# Filtrado_y_amplificaci_n.net
KiCad netlist of a schematic drawn in Altium Designer
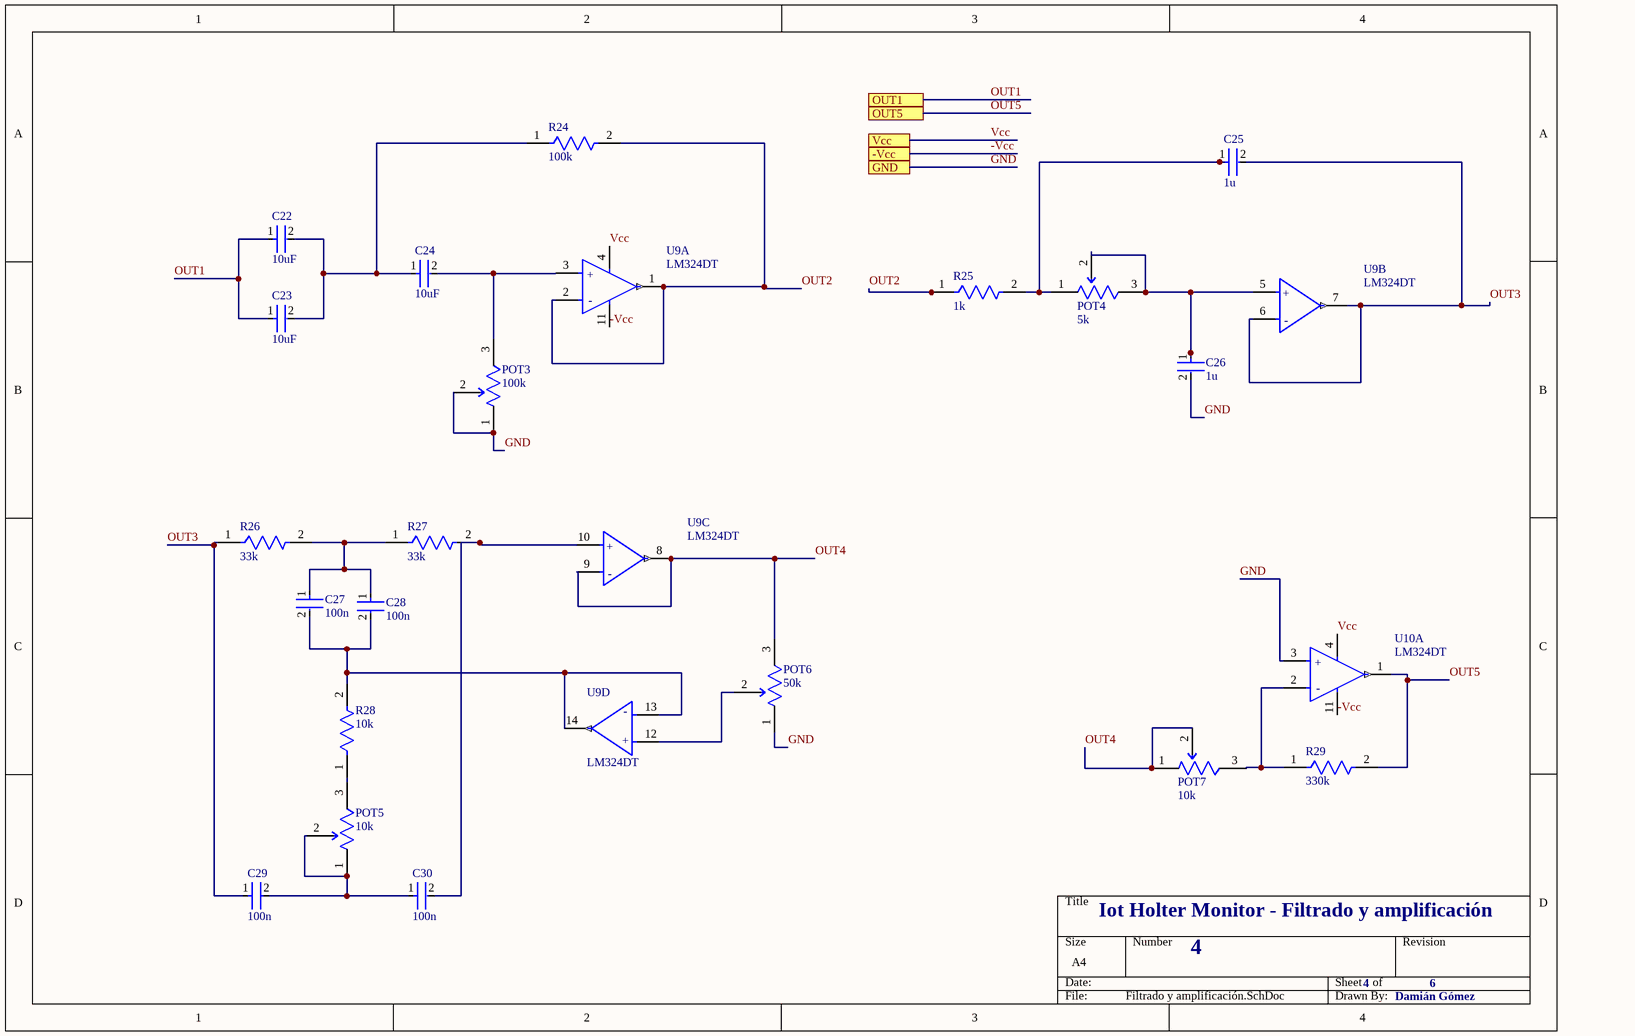
[diagram p0: Filtrado y amplificación.SchDoc]

(export (version "E")
  (design (tool "Eeschema 10.0.6"))
  (components
    (comp (ref "C22")
      (value "10uF")
      (footprint "FP-CL31-IPC_C")
      (description "Cap Ceramic 10uF 500V C0G ±5% SMD 1206 +125°C Embossed T/R")
      (fields (field (name "TOLERANCE") "5%"))
      (libsource (lib "Altium Content Vault") (part "b4654b650e69147ec39a6b967a45e02"))
    )
    (comp (ref "C23")
      (value "10uF")
      (footprint "FP-CL31-IPC_C")
      (description "Cap Ceramic 10uF 500V C0G ±5% SMD 1206 +125°C Embossed T/R")
      (fields (field (name "TOLERANCE") "5%"))
      (libsource (lib "Altium Content Vault") (part "b4654b650e69147ec39a6b967a45e02"))
    )
    (comp (ref "C24")
      (value "10uF")
      (footprint "FP-CL31-IPC_C")
      (description "Cap Ceramic 10uF 500V C0G ±5% SMD 1206 +125°C Embossed T/R")
      (fields (field (name "TOLERANCE") "5%"))
      (libsource (lib "Altium Content Vault") (part "b4654b650e69147ec39a6b967a45e02"))
    )
    (comp (ref "C25")
      (value "1u")
      (footprint "FP-CL31-IPC_C")
      (description "Cap Ceramic 1uF 500V C0G ±5% SMD 1206 +125°C Embossed T/R")
      (fields (field (name "TOLERANCE") "5%"))
      (libsource (lib "Altium Content Vault") (part "b4654b650e69147ec39a6b967a45e02"))
    )
    (comp (ref "C26")
      (value "1u")
      (footprint "FP-CL31-IPC_C")
      (description "Cap Ceramic 1uF 500V C0G ±5% SMD 1206 +125°C Embossed T/R")
      (fields (field (name "TOLERANCE") "5%"))
      (libsource (lib "Altium Content Vault") (part "b4654b650e69147ec39a6b967a45e02"))
    )
    (comp (ref "C27")
      (value "100n")
      (footprint "FP-CL31-IPC_C")
      (description "Cap Ceramic 100nF 500V C0G ±5% SMD 1206 +125°C Embossed T/R")
      (fields (field (name "TOLERANCE") "5%"))
      (libsource (lib "Altium Content Vault") (part "b4654b650e69147ec39a6b967a45e02"))
    )
    (comp (ref "C28")
      (value "100n")
      (footprint "FP-CL31-IPC_C")
      (description "Cap Ceramic 100nF 500V C0G ±5% SMD 1206 +125°C Embossed T/R")
      (fields (field (name "TOLERANCE") "5%"))
      (libsource (lib "Altium Content Vault") (part "b4654b650e69147ec39a6b967a45e02"))
    )
    (comp (ref "C29")
      (value "100n")
      (footprint "FP-CL31-IPC_C")
      (description "Cap Ceramic 100nF 500V C0G ±5% SMD 1206 +125°C Embossed T/R")
      (fields (field (name "TOLERANCE") "5%"))
      (libsource (lib "Altium Content Vault") (part "b4654b650e69147ec39a6b967a45e02"))
    )
    (comp (ref "C30")
      (value "100n")
      (footprint "FP-CL31-IPC_C")
      (description "Cap Ceramic 100nF 500V C0G ±5% SMD 1206 +125°C Embossed T/R")
      (fields (field (name "TOLERANCE") "5%"))
      (libsource (lib "Altium Content Vault") (part "b4654b650e69147ec39a6b967a45e02"))
    )
    (comp (ref "POT3")
      (value "100k")
      (footprint "FP-3296W-MFG")
      (description "TRIMMER 100K OHM 0.5W PC PIN TOP")
      (fields (field (name "TOLERANCE") "10%"))
      (libsource (lib "Altium Content Vault") (part "194907ebf2981c0cdd5d9631a0af656"))
    )
    (comp (ref "POT4")
      (value "5k")
      (footprint "FP-3296W-MFG")
      (description "TRIMMER 5K OHM 0.5W PC PIN TOP")
      (fields (field (name "TOLERANCE") "10%"))
      (libsource (lib "Altium Content Vault") (part "194907ebf2981c0cdd5d9631a0af656"))
    )
    (comp (ref "POT5")
      (value "10k")
      (footprint "FP-3296W-MFG")
      (description "TRIMMER 10K OHM 0.5W PC PIN TOP")
      (fields (field (name "TOLERANCE") "10%"))
      (libsource (lib "Altium Content Vault") (part "194907ebf2981c0cdd5d9631a0af656"))
    )
    (comp (ref "POT6")
      (value "50k")
      (footprint "FP-3296W-MFG")
      (description "TRIMMER 50K OHM 0.5W PC PIN TOP")
      (fields (field (name "TOLERANCE") "10%"))
      (libsource (lib "Altium Content Vault") (part "194907ebf2981c0cdd5d9631a0af656"))
    )
    (comp (ref "POT7")
      (value "10k")
      (footprint "FP-3296W-MFG")
      (description "TRIMMER 10K OHM 0.5W PC PIN TOP")
      (fields (field (name "TOLERANCE") "10%"))
      (libsource (lib "Altium Content Vault") (part "194907ebf2981c0cdd5d9631a0af656"))
    )
    (comp (ref "R24")
      (value "100k")
      (footprint "FP-RC3216-MFG")
      (description "Res Thick Film 1206 1kΩ 5% 0.25W ±100ppm/°C Molded SMD T/R")
      (fields (field (name "TOLERANCE") "5%"))
      (libsource (lib "Altium Content Vault") (part "1029c3af85768c4190bb7ad29bc67b5"))
    )
    (comp (ref "R25")
      (value "1k")
      (footprint "FP-RC3216-MFG")
      (description "Res Thick Film 1206 1kΩ 5% 0.25W ±100ppm/°C Molded SMD T/R")
      (fields (field (name "TOLERANCE") "5%"))
      (libsource (lib "Altium Content Vault") (part "1029c3af85768c4190bb7ad29bc67b5"))
    )
    (comp (ref "R26")
      (value "33k")
      (footprint "FP-RC3216-MFG")
      (description "Res Thick Film 1206 33kΩ 5% 0.25W ±100ppm/°C Molded SMD T/R")
      (fields (field (name "TOLERANCE") "5%"))
      (libsource (lib "Altium Content Vault") (part "1029c3af85768c4190bb7ad29bc67b5"))
    )
    (comp (ref "R27")
      (value "33k")
      (footprint "FP-RC3216-MFG")
      (description "Res Thick Film 1206 33kΩ 5% 0.25W ±100ppm/°C Molded SMD T/R")
      (fields (field (name "TOLERANCE") "5%"))
      (libsource (lib "Altium Content Vault") (part "1029c3af85768c4190bb7ad29bc67b5"))
    )
    (comp (ref "R28")
      (value "10k")
      (footprint "FP-RC3216-MFG")
      (description "Res Thick Film 1206 10kΩ 5% 0.25W ±100ppm/°C Molded SMD T/R")
      (fields (field (name "TOLERANCE") "5%"))
      (libsource (lib "Altium Content Vault") (part "1029c3af85768c4190bb7ad29bc67b5"))
    )
    (comp (ref "R29")
      (value "330k")
      (footprint "FP-RC3216-MFG")
      (description "Res Thick Film 1206 330kΩ 5% 0.25W ±100ppm/°C Molded SMD T/R")
      (fields (field (name "TOLERANCE") "5%"))
      (libsource (lib "Altium Content Vault") (part "1029c3af85768c4190bb7ad29bc67b5"))
    )
    (comp (ref "U9")
      (value "LM324DT")
      (footprint "FP-SO-14-MFG")
      (description "IC OPAMP GP 4 CIRCUIT 14SO")
      (fields
        (field (name "OCTOPART") "https://octopart.com/lm324dt-stmicroelectronics-39579146")
        (field (name "MANUFACTURER") "STMicroelectronics")
      )
      (libsource (lib "Altium Content Vault") (part "a065ef67e5aa9ef3942d43d6008d043"))
    )
    (comp (ref "U10")
      (value "LM324DT")
      (footprint "FP-SO-14-MFG")
      (description "IC OPAMP GP 4 CIRCUIT 14SO")
      (fields
        (field (name "OCTOPART") "https://octopart.com/lm324dt-stmicroelectronics-39579146")
        (field (name "MANUFACTURER") "STMicroelectronics")
      )
      (libsource (lib "Altium Content Vault") (part "a065ef67e5aa9ef3942d43d6008d043"))
    )
  )
  (nets
    (net (code "1") (name "/-Vcc") (class "Default")
      (node (ref "U10") (pin "11") (pinfunction "VCC-_11") (pintype "power_in"))
      (node (ref "U9") (pin "11") (pinfunction "VCC-_11") (pintype "power_in"))
    )
    (net (code "2") (name "/GND") (class "Default")
      (node (ref "C26") (pin "2") (pinfunction "2_2") (pintype "passive"))
      (node (ref "POT3") (pin "1") (pinfunction "CCW_1") (pintype "passive"))
      (node (ref "POT3") (pin "2") (pinfunction "WIPER_2") (pintype "passive"))
      (node (ref "POT6") (pin "1") (pinfunction "CCW_1") (pintype "passive"))
      (node (ref "U10") (pin "3") (pinfunction "Non-Inverting_Input_1_3") (pintype "tri_state"))
    )
    (net (code "3") (name "/OUT1") (class "Default")
      (node (ref "C22") (pin "1") (pinfunction "1_1") (pintype "passive"))
      (node (ref "C23") (pin "1") (pinfunction "1_1") (pintype "passive"))
    )
    (net (code "4") (name "/OUT2") (class "Default")
      (node (ref "R24") (pin "2") (pinfunction "2_2") (pintype "passive"))
      (node (ref "R25") (pin "1") (pinfunction "1_1") (pintype "passive"))
      (node (ref "U9") (pin "1") (pinfunction "Output_1_1") (pintype "output"))
      (node (ref "U9") (pin "2") (pinfunction "Inverting_Input_1_2") (pintype "tri_state"))
    )
    (net (code "5") (name "/OUT3") (class "Default")
      (node (ref "C25") (pin "2") (pinfunction "2_2") (pintype "passive"))
      (node (ref "C29") (pin "1") (pinfunction "1_1") (pintype "passive"))
      (node (ref "R26") (pin "1") (pinfunction "1_1") (pintype "passive"))
      (node (ref "U9") (pin "6") (pinfunction "Inverting_Input_2_6") (pintype "tri_state"))
      (node (ref "U9") (pin "7") (pinfunction "Output_2_7") (pintype "output"))
    )
    (net (code "6") (name "/OUT4") (class "Default")
      (node (ref "POT6") (pin "3") (pinfunction "CW_3") (pintype "passive"))
      (node (ref "POT7") (pin "1") (pinfunction "CCW_1") (pintype "passive"))
      (node (ref "POT7") (pin "2") (pinfunction "WIPER_2") (pintype "passive"))
      (node (ref "U9") (pin "8") (pinfunction "Output_3_8") (pintype "output"))
      (node (ref "U9") (pin "9") (pinfunction "Inverting_Input_3_9") (pintype "tri_state"))
    )
    (net (code "7") (name "/OUT5") (class "Default")
      (node (ref "R29") (pin "2") (pinfunction "2_2") (pintype "passive"))
      (node (ref "U10") (pin "1") (pinfunction "Output_1_1") (pintype "output"))
    )
    (net (code "8") (name "/Vcc") (class "Default")
      (node (ref "U10") (pin "4") (pinfunction "VCC+_4") (pintype "power_in"))
      (node (ref "U9") (pin "4") (pinfunction "VCC+_4") (pintype "power_in"))
    )
    (net (code "9") (name "Net-(C22-Pad2)") (class "Default")
      (node (ref "C22") (pin "2") (pinfunction "2_2") (pintype "passive"))
      (node (ref "C23") (pin "2") (pinfunction "2_2") (pintype "passive"))
      (node (ref "C24") (pin "1") (pinfunction "1_1") (pintype "passive"))
      (node (ref "R24") (pin "1") (pinfunction "1_1") (pintype "passive"))
    )
    (net (code "10") (name "Net-(C27-Pad1)") (class "Default")
      (node (ref "C27") (pin "1") (pinfunction "1_1") (pintype "passive"))
      (node (ref "C28") (pin "1") (pinfunction "1_1") (pintype "passive"))
      (node (ref "R26") (pin "2") (pinfunction "2_2") (pintype "passive"))
      (node (ref "R27") (pin "1") (pinfunction "1_1") (pintype "passive"))
    )
    (net (code "11") (name "Net-(POT3-CW)") (class "Default")
      (node (ref "C24") (pin "2") (pinfunction "2_2") (pintype "passive"))
      (node (ref "POT3") (pin "3") (pinfunction "CW_3") (pintype "passive"))
      (node (ref "U9") (pin "3") (pinfunction "Non-Inverting_Input_1_3") (pintype "tri_state"))
    )
    (net (code "12") (name "Net-(POT4-CCW)") (class "Default")
      (node (ref "C25") (pin "1") (pinfunction "1_1") (pintype "passive"))
      (node (ref "POT4") (pin "1") (pinfunction "CCW_1") (pintype "passive"))
      (node (ref "R25") (pin "2") (pinfunction "2_2") (pintype "passive"))
    )
    (net (code "13") (name "Net-(POT4-CW)") (class "Default")
      (node (ref "C26") (pin "1") (pinfunction "1_1") (pintype "passive"))
      (node (ref "POT4") (pin "2") (pinfunction "WIPER_2") (pintype "passive"))
      (node (ref "POT4") (pin "3") (pinfunction "CW_3") (pintype "passive"))
      (node (ref "U9") (pin "5") (pinfunction "Non-Inverting_Input_2_5") (pintype "tri_state"))
    )
    (net (code "14") (name "Net-(POT5-CCW)") (class "Default")
      (node (ref "C29") (pin "2") (pinfunction "2_2") (pintype "passive"))
      (node (ref "C30") (pin "1") (pinfunction "1_1") (pintype "passive"))
      (node (ref "POT5") (pin "1") (pinfunction "CCW_1") (pintype "passive"))
      (node (ref "POT5") (pin "2") (pinfunction "WIPER_2") (pintype "passive"))
    )
    (net (code "15") (name "Net-(POT5-CW)") (class "Default")
      (node (ref "POT5") (pin "3") (pinfunction "CW_3") (pintype "passive"))
      (node (ref "R28") (pin "1") (pinfunction "1_1") (pintype "passive"))
    )
    (net (code "16") (name "Net-(POT6-WIPER)") (class "Default")
      (node (ref "POT6") (pin "2") (pinfunction "WIPER_2") (pintype "passive"))
      (node (ref "U9") (pin "12") (pinfunction "Non-Inverting_Input_4_12") (pintype "tri_state"))
    )
    (net (code "17") (name "Net-(POT7-CW)") (class "Default")
      (node (ref "POT7") (pin "3") (pinfunction "CW_3") (pintype "passive"))
      (node (ref "R29") (pin "1") (pinfunction "1_1") (pintype "passive"))
      (node (ref "U10") (pin "2") (pinfunction "Inverting_Input_1_2") (pintype "tri_state"))
    )
    (net (code "18") (name "Net-(U9C-Non-Inverting_Input_3)") (class "Default")
      (node (ref "C30") (pin "2") (pinfunction "2_2") (pintype "passive"))
      (node (ref "R27") (pin "2") (pinfunction "2_2") (pintype "passive"))
      (node (ref "U9") (pin "10") (pinfunction "Non-Inverting_Input_3_10") (pintype "tri_state"))
    )
    (net (code "19") (name "Net-(U9D-Inverting_Input_4)") (class "Default")
      (node (ref "C27") (pin "2") (pinfunction "2_2") (pintype "passive"))
      (node (ref "C28") (pin "2") (pinfunction "2_2") (pintype "passive"))
      (node (ref "R28") (pin "2") (pinfunction "2_2") (pintype "passive"))
      (node (ref "U9") (pin "13") (pinfunction "Inverting_Input_4_13") (pintype "passive"))
      (node (ref "U9") (pin "14") (pinfunction "Output_4_14") (pintype "output"))
    )
  )
)
